# FIDO2AUTH_002.net
KiCad netlist of a schematic drawn in EAGLE
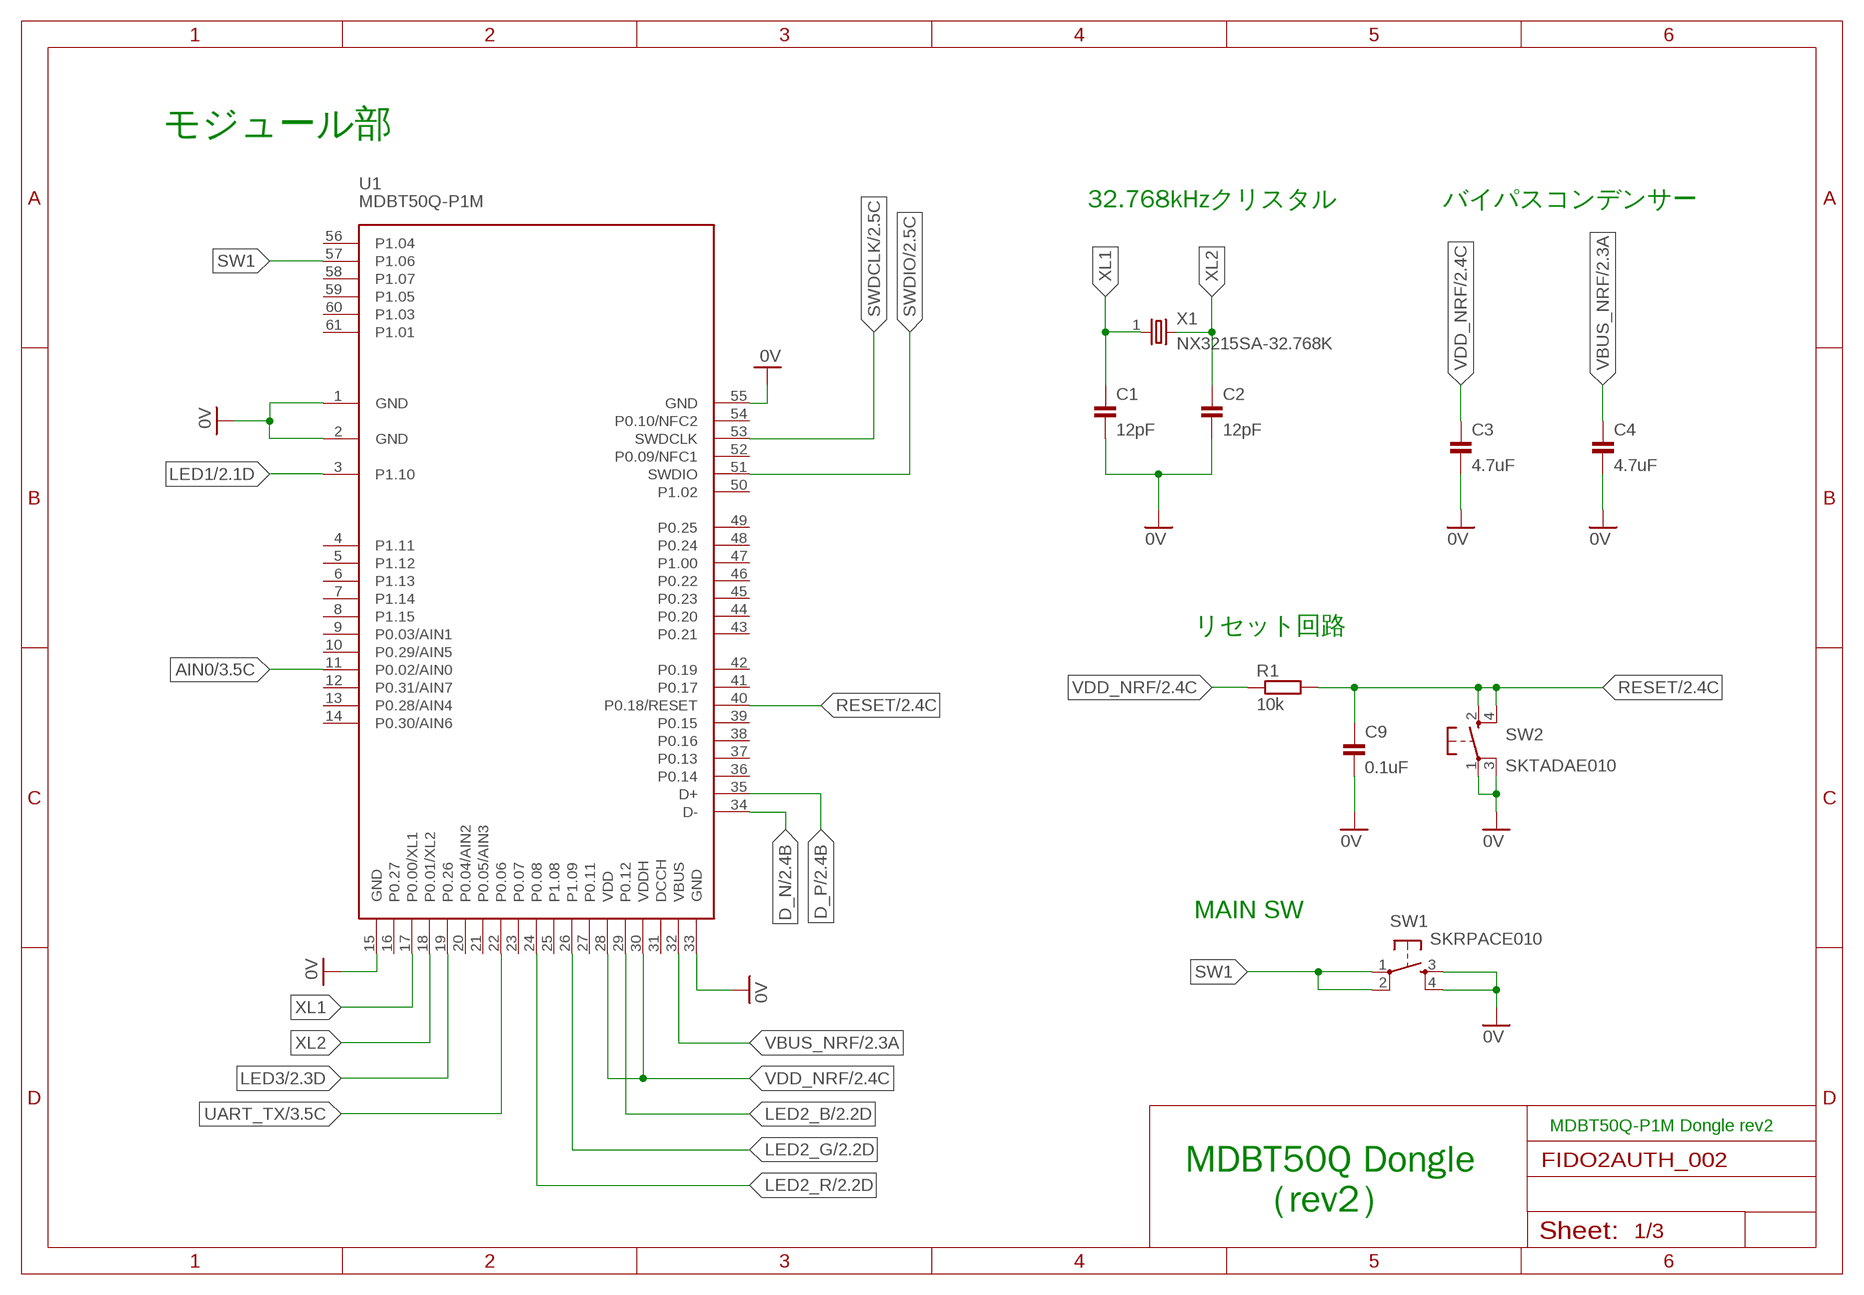
[diagram p0: schematic, sheet 1]
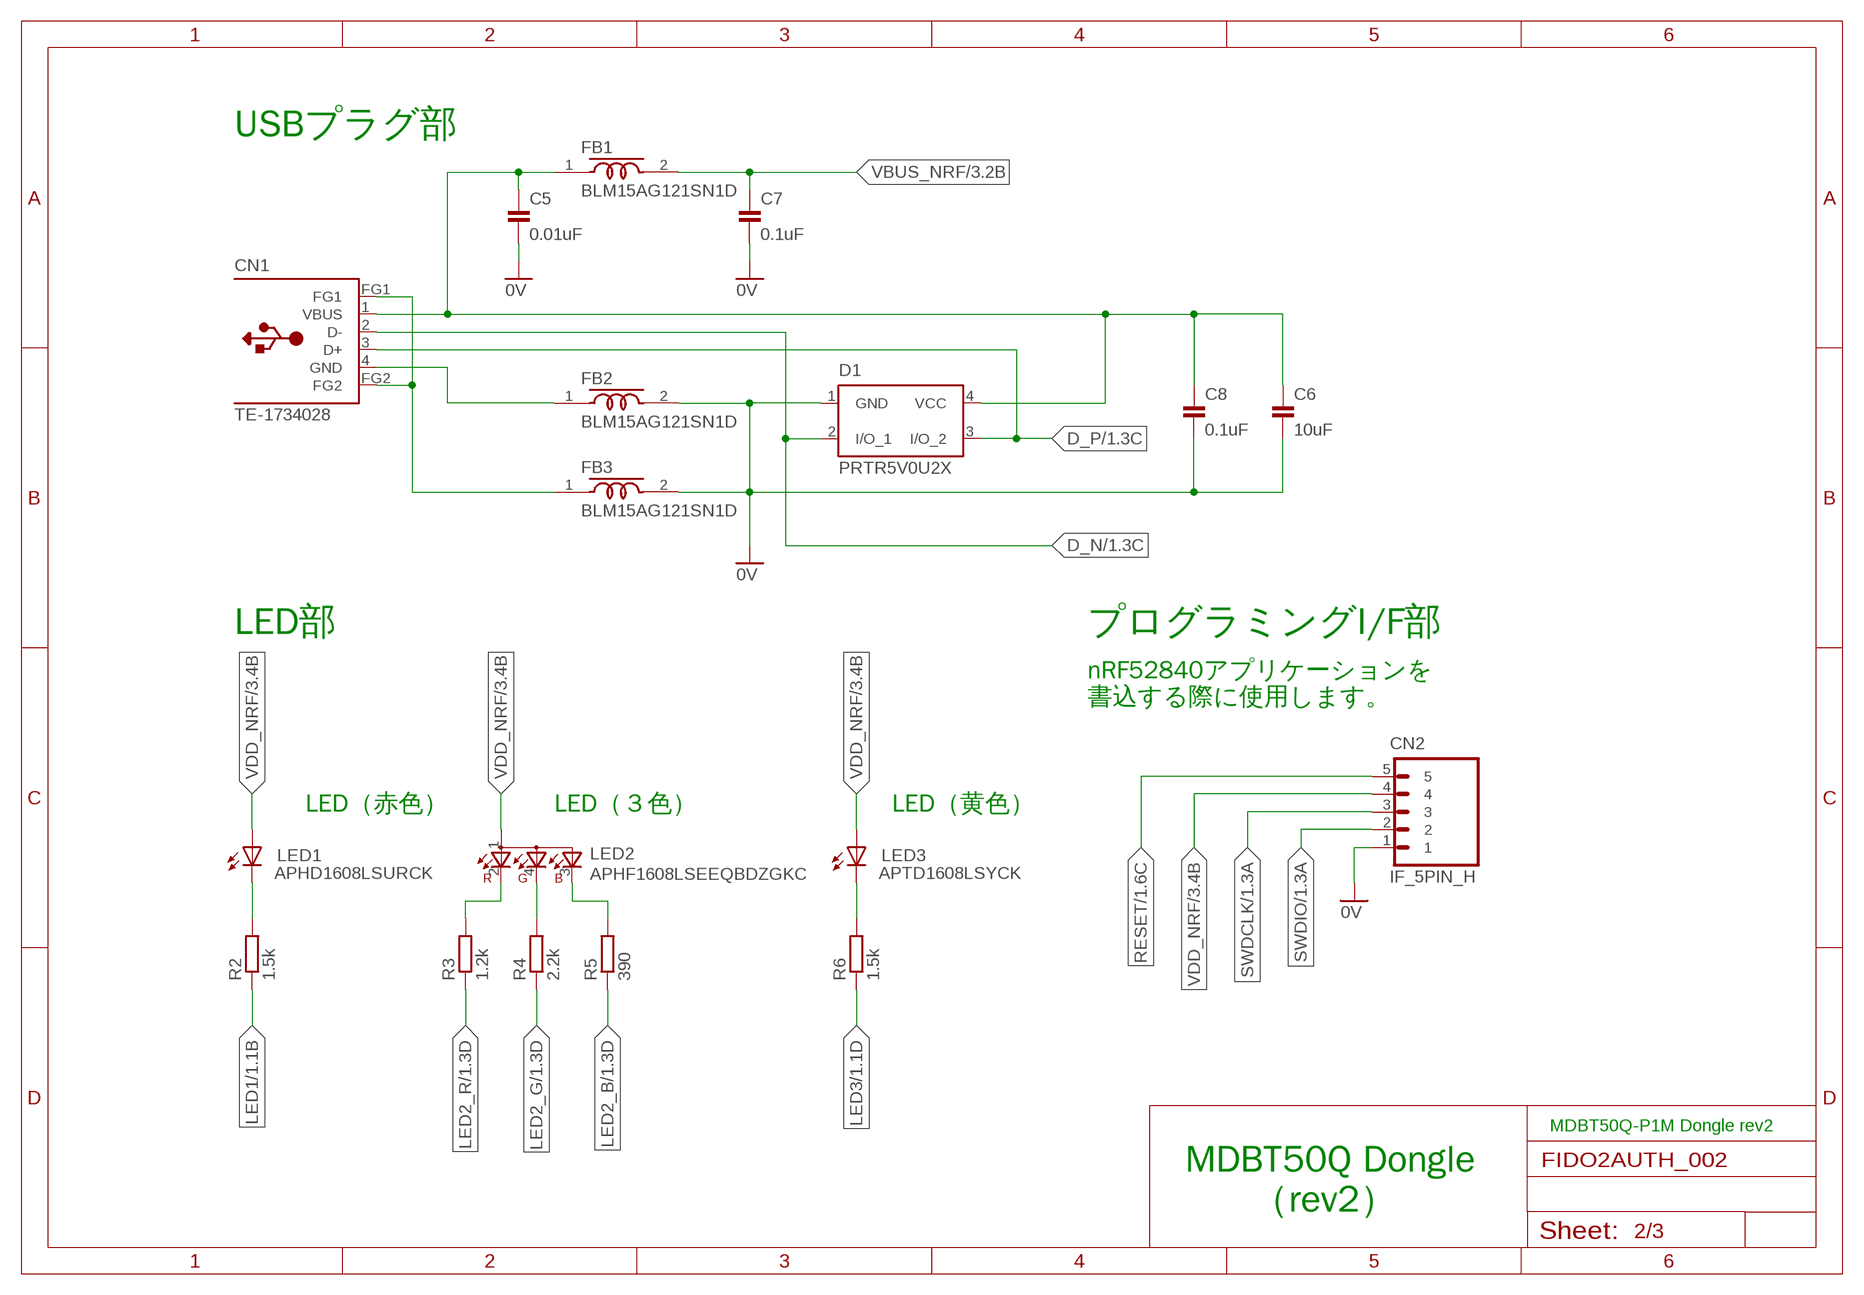
[diagram p1: schematic, sheet 2]
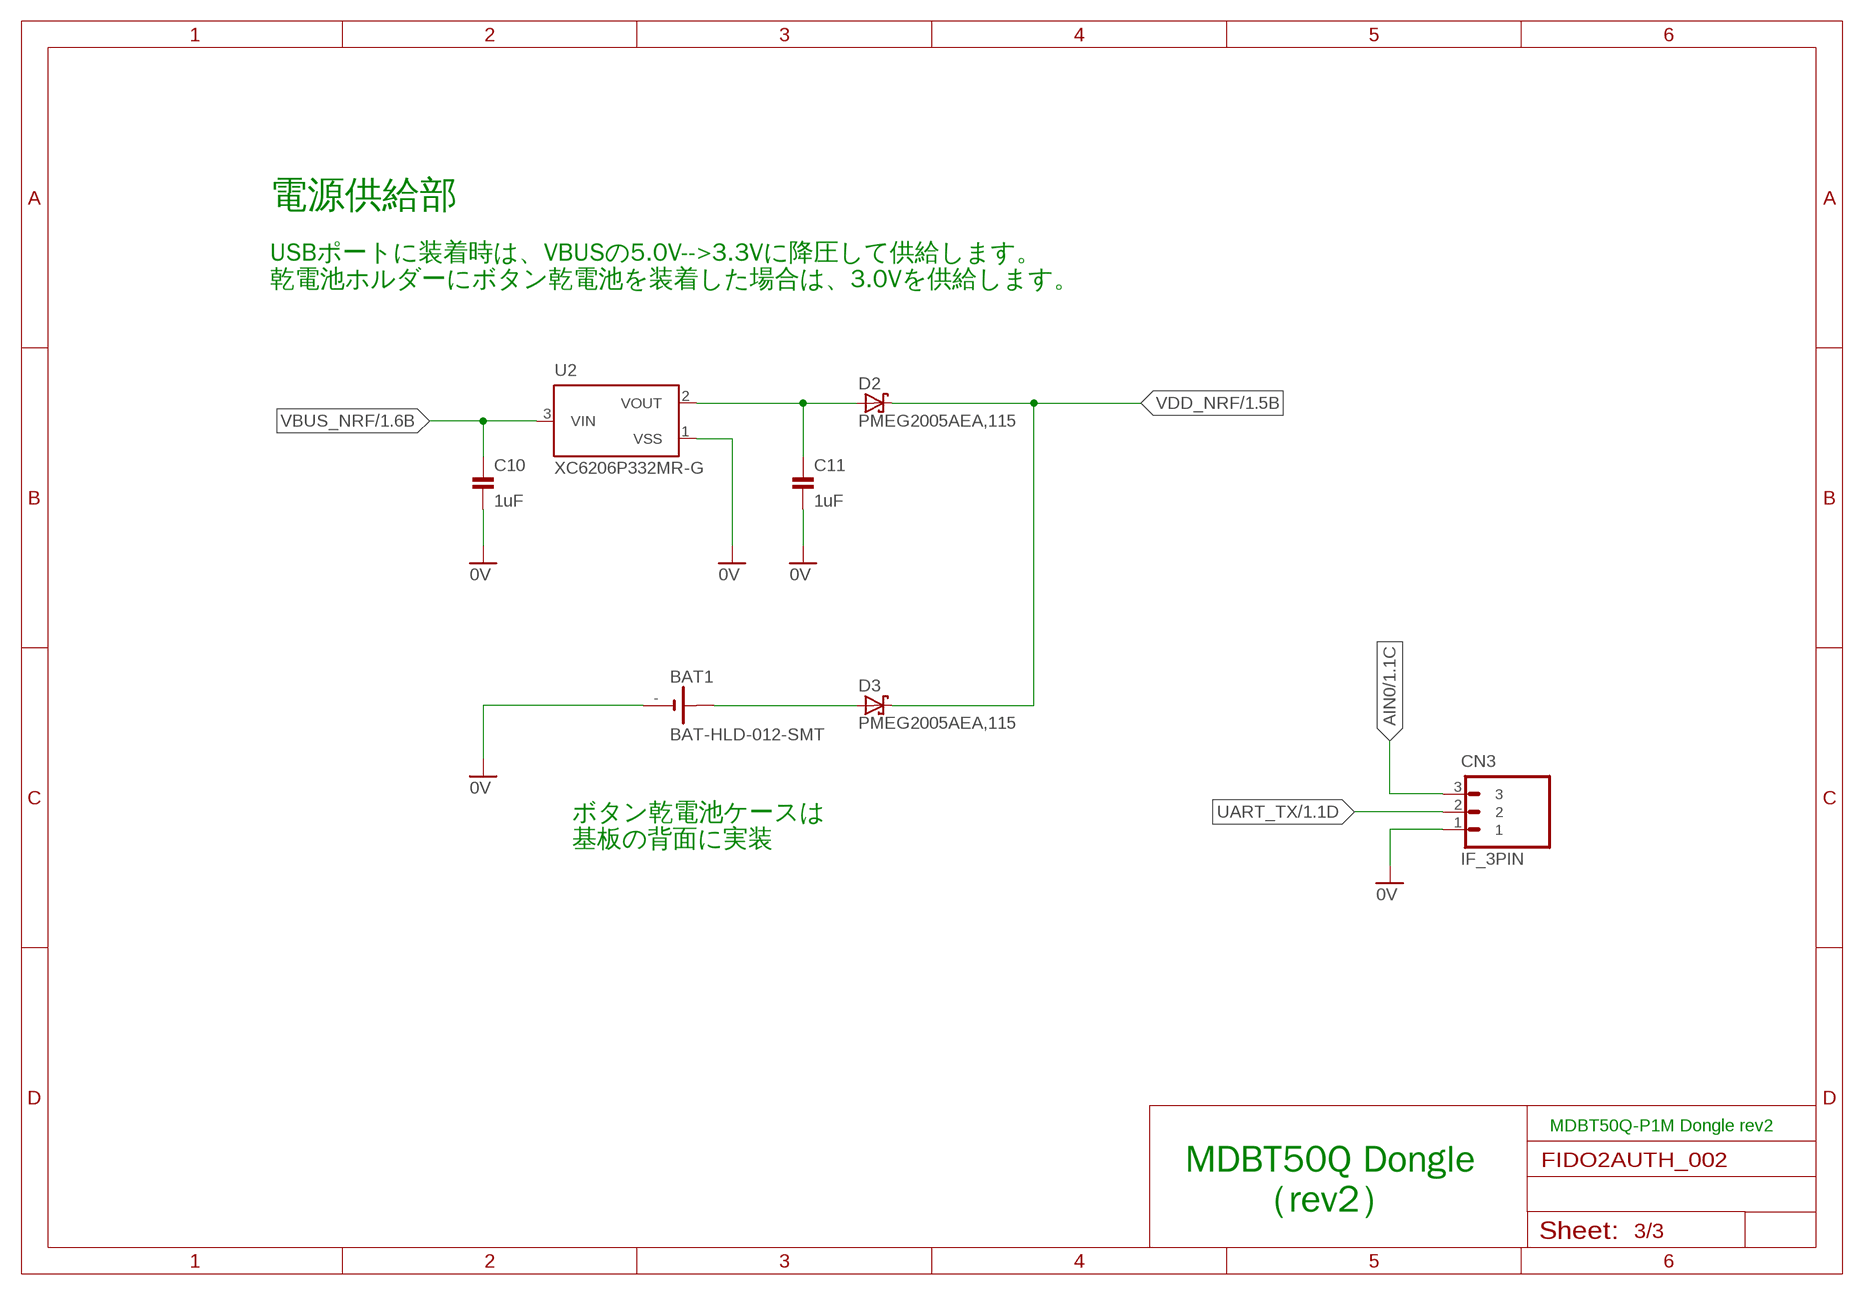
[diagram p2: schematic, sheet 3]

(export (version "E")
  (design (tool "Eeschema 10.0.6"))
  (components
    (comp (ref "BAT1")
      (value "BAT-HLD-012-SMT")
      (footprint "eagle-import:BAT-HLD-012-SMT")
      (libsource (lib "eagle-import") (part "BAT-HLD-012-SMT"))
    )
    (comp (ref "C10")
      (value "1uF")
      (footprint "eagle-import:C0603K")
      (libsource (lib "eagle-import") (part "CAP_0603"))
    )
    (comp (ref "C11")
      (value "1uF")
      (footprint "eagle-import:C0603K")
      (libsource (lib "eagle-import") (part "CAP_0603"))
    )
    (comp (ref "CN3")
      (value "IF_3PIN")
      (footprint "eagle-import:HEADER_3PIN")
      (libsource (lib "eagle-import") (part "IF_3PIN"))
    )
    (comp (ref "D2")
      (value "PMEG2005AEA,115")
      (footprint "eagle-import:SOD323-W")
      (libsource (lib "eagle-import") (part "PMEG2005AEA,115"))
    )
    (comp (ref "D3")
      (value "PMEG2005AEA,115")
      (footprint "eagle-import:SOD323-W")
      (libsource (lib "eagle-import") (part "PMEG2005AEA,115"))
    )
    (comp (ref "U2")
      (value "XC6206P332MR-G")
      (footprint "eagle-import:SOT23")
      (libsource (lib "eagle-import") (part "XC6206P332MR-G"))
    )
    (comp (ref "C5")
      (value "0.01uF")
      (footprint "eagle-import:C0603K")
      (libsource (lib "eagle-import") (part "CAP_0603"))
    )
    (comp (ref "C6")
      (value "10uF")
      (footprint "eagle-import:C0603K")
      (libsource (lib "eagle-import") (part "CAP_0603"))
    )
    (comp (ref "C7")
      (value "0.1uF")
      (footprint "eagle-import:C0603K")
      (libsource (lib "eagle-import") (part "CAP_0603"))
    )
    (comp (ref "C8")
      (value "0.1uF")
      (footprint "eagle-import:C0603K")
      (libsource (lib "eagle-import") (part "CAP_0603"))
    )
    (comp (ref "CN1")
      (value "TE-1734028")
      (footprint "eagle-import:TE-1734028")
      (libsource (lib "eagle-import") (part "TE-1734028"))
    )
    (comp (ref "CN2")
      (value "IF_5PIN_H")
      (footprint "eagle-import:HEADER_5PIN")
      (libsource (lib "eagle-import") (part "IF_5PIN_H"))
    )
    (comp (ref "D1")
      (value "PRTR5V0U2X")
      (footprint "eagle-import:SOT143B")
      (libsource (lib "eagle-import") (part "PRTR5V0U2X"))
    )
    (comp (ref "FB1")
      (value "BLM15AG121SN1D")
      (footprint "eagle-import:C0402K@1")
      (libsource (lib "eagle-import") (part "BLM15AG121SN1D"))
    )
    (comp (ref "FB2")
      (value "BLM15AG121SN1D")
      (footprint "eagle-import:C0402K@1")
      (libsource (lib "eagle-import") (part "BLM15AG121SN1D"))
    )
    (comp (ref "FB3")
      (value "BLM15AG121SN1D")
      (footprint "eagle-import:C0402K@1")
      (libsource (lib "eagle-import") (part "BLM15AG121SN1D"))
    )
    (comp (ref "LED1")
      (value "APHD1608LSURCK")
      (footprint "eagle-import:CHIPLED_0603")
      (libsource (lib "eagle-import") (part "APHD1608LSURCK"))
    )
    (comp (ref "LED2")
      (value "APHF1608LSEEQBDZGKC")
      (footprint "eagle-import:APHF1608LSEEQBDZGKC")
      (libsource (lib "eagle-import") (part "APHF1608LSEEQBDZGKC"))
    )
    (comp (ref "LED3")
      (value "APTD1608LSYCK")
      (footprint "eagle-import:CHIPLED_0603")
      (libsource (lib "eagle-import") (part "APTD1608LSYCK"))
    )
    (comp (ref "R2")
      (value "1.5k")
      (footprint "eagle-import:R0603")
      (libsource (lib "eagle-import") (part "RESISTOR_0603"))
    )
    (comp (ref "R3")
      (value "1.2k")
      (footprint "eagle-import:R0603")
      (libsource (lib "eagle-import") (part "RESISTOR_0603"))
    )
    (comp (ref "R4")
      (value "2.2k")
      (footprint "eagle-import:R0603")
      (libsource (lib "eagle-import") (part "RESISTOR_0603"))
    )
    (comp (ref "R5")
      (value "390")
      (footprint "eagle-import:R0603")
      (libsource (lib "eagle-import") (part "RESISTOR_0603"))
    )
    (comp (ref "R6")
      (value "1.5k")
      (footprint "eagle-import:R0603")
      (libsource (lib "eagle-import") (part "RESISTOR_0603"))
    )
    (comp (ref "C1")
      (value "12pF")
      (footprint "eagle-import:C0603K")
      (libsource (lib "eagle-import") (part "CAP_0603"))
    )
    (comp (ref "C2")
      (value "12pF")
      (footprint "eagle-import:C0603K")
      (libsource (lib "eagle-import") (part "CAP_0603"))
    )
    (comp (ref "C3")
      (value "4.7uF")
      (footprint "eagle-import:C0603K")
      (libsource (lib "eagle-import") (part "CAP_0603"))
    )
    (comp (ref "C4")
      (value "4.7uF")
      (footprint "eagle-import:C0603K")
      (libsource (lib "eagle-import") (part "CAP_0603"))
    )
    (comp (ref "C9")
      (value "0.1uF")
      (footprint "eagle-import:C0603K")
      (libsource (lib "eagle-import") (part "CAP_0603"))
    )
    (comp (ref "R1")
      (value "10k")
      (footprint "eagle-import:R0603")
      (libsource (lib "eagle-import") (part "RESISTOR_0603"))
    )
    (comp (ref "SW1")
      (value "SKRPACE010")
      (footprint "eagle-import:SKRPACE010")
      (libsource (lib "eagle-import") (part "SKRPACE010"))
    )
    (comp (ref "SW2")
      (value "SKTADAE010")
      (footprint "eagle-import:SKTADAE010")
      (libsource (lib "eagle-import") (part "SKTADAE010"))
    )
    (comp (ref "U1")
      (value "MDBT50Q-P1M")
      (footprint "eagle-import:MDBT50Q-P1M")
      (libsource (lib "eagle-import") (part "MDBT50Q-P1M"))
    )
    (comp (ref "X1")
      (value "NX3215SA-32.768K")
      (footprint "eagle-import:NX3215")
      (libsource (lib "eagle-import") (part "NX3215SA-32.768K"))
    )
  )
  (nets
    (net (code "1") (name "0V") (class "Default")
      (node (ref "BAT1") (pin "-") (pinfunction "-_-") (pintype "passive"))
      (node (ref "C1") (pin "2") (pinfunction "2_2") (pintype "passive"))
      (node (ref "C10") (pin "2") (pinfunction "2_2") (pintype "passive"))
      (node (ref "C11") (pin "2") (pinfunction "2_2") (pintype "passive"))
      (node (ref "C2") (pin "2") (pinfunction "2_2") (pintype "passive"))
      (node (ref "C3") (pin "2") (pinfunction "2_2") (pintype "passive"))
      (node (ref "C4") (pin "2") (pinfunction "2_2") (pintype "passive"))
      (node (ref "C5") (pin "2") (pinfunction "2_2") (pintype "passive"))
      (node (ref "C6") (pin "2") (pinfunction "2_2") (pintype "passive"))
      (node (ref "C7") (pin "2") (pinfunction "2_2") (pintype "passive"))
      (node (ref "C8") (pin "2") (pinfunction "2_2") (pintype "passive"))
      (node (ref "C9") (pin "2") (pinfunction "2_2") (pintype "passive"))
      (node (ref "CN2") (pin "1") (pinfunction "1_1") (pintype "passive"))
      (node (ref "CN3") (pin "1") (pinfunction "1_1") (pintype "passive"))
      (node (ref "D1") (pin "1") (pinfunction "GND_1") (pintype "passive"))
      (node (ref "FB2") (pin "2") (pinfunction "2_2") (pintype "passive"))
      (node (ref "FB3") (pin "2") (pinfunction "2_2") (pintype "passive"))
      (node (ref "SW1") (pin "3") (pinfunction "S_3") (pintype "passive"))
      (node (ref "SW1") (pin "4") (pinfunction "S1_4") (pintype "passive"))
      (node (ref "SW2") (pin "1") (pinfunction "P_1") (pintype "passive"))
      (node (ref "SW2") (pin "3") (pinfunction "P1_3") (pintype "passive"))
      (node (ref "U1") (pin "1") (pinfunction "GND_1") (pintype "bidirectional"))
      (node (ref "U1") (pin "15") (pinfunction "GND_15") (pintype "bidirectional"))
      (node (ref "U1") (pin "2") (pinfunction "GND_2") (pintype "bidirectional"))
      (node (ref "U1") (pin "33") (pinfunction "GND_33") (pintype "bidirectional"))
      (node (ref "U1") (pin "55") (pinfunction "GND_55") (pintype "bidirectional"))
      (node (ref "U2") (pin "1") (pinfunction "VSS_1") (pintype "passive"))
    )
    (net (code "2") (name "AIN0") (class "Default")
      (node (ref "CN3") (pin "3") (pinfunction "3_3") (pintype "passive"))
      (node (ref "U1") (pin "11") (pinfunction "P0.02/AIN0_11") (pintype "bidirectional"))
    )
    (net (code "3") (name "D_N") (class "Default")
      (node (ref "CN1") (pin "2") (pinfunction "D-_2") (pintype "bidirectional"))
      (node (ref "D1") (pin "2") (pinfunction "I/O_1_2") (pintype "bidirectional"))
      (node (ref "U1") (pin "34") (pinfunction "D-_34") (pintype "bidirectional"))
    )
    (net (code "4") (name "D_P") (class "Default")
      (node (ref "CN1") (pin "3") (pinfunction "D+_3") (pintype "bidirectional"))
      (node (ref "D1") (pin "3") (pinfunction "I/O_2_3") (pintype "bidirectional"))
      (node (ref "U1") (pin "35") (pinfunction "D+_35") (pintype "bidirectional"))
    )
    (net (code "5") (name "LED1") (class "Default")
      (node (ref "R2") (pin "1") (pinfunction "1_1") (pintype "passive"))
      (node (ref "U1") (pin "3") (pinfunction "P1.10_3") (pintype "bidirectional"))
    )
    (net (code "6") (name "LED2_B") (class "Default")
      (node (ref "R5") (pin "1") (pinfunction "1_1") (pintype "passive"))
      (node (ref "U1") (pin "29") (pinfunction "P0.12_29") (pintype "bidirectional"))
    )
    (net (code "7") (name "LED2_G") (class "Default")
      (node (ref "R4") (pin "1") (pinfunction "1_1") (pintype "passive"))
      (node (ref "U1") (pin "26") (pinfunction "P1.09_26") (pintype "bidirectional"))
    )
    (net (code "8") (name "LED2_R") (class "Default")
      (node (ref "R3") (pin "1") (pinfunction "1_1") (pintype "passive"))
      (node (ref "U1") (pin "24") (pinfunction "P0.08_24") (pintype "bidirectional"))
    )
    (net (code "9") (name "LED3") (class "Default")
      (node (ref "R6") (pin "1") (pinfunction "1_1") (pintype "passive"))
      (node (ref "U1") (pin "19") (pinfunction "P0.26_19") (pintype "bidirectional"))
    )
    (net (code "10") (name "Net-(BAT1-+)") (class "Default")
      (node (ref "BAT1") (pin "+@1") (pinfunction "+_+@1") (pintype "passive"))
      (node (ref "D3") (pin "A") (pinfunction "A_A") (pintype "passive"))
    )
    (net (code "11") (name "Net-(CN1-GND)") (class "Default")
      (node (ref "CN1") (pin "4") (pinfunction "GND_4") (pintype "passive"))
      (node (ref "FB2") (pin "1") (pinfunction "1_1") (pintype "passive"))
    )
    (net (code "12") (name "Net-(CN1-PadFG1)") (class "Default")
      (node (ref "CN1") (pin "FG1") (pinfunction "FG1_FG1") (pintype "passive"))
      (node (ref "CN1") (pin "FG2") (pinfunction "FG2_FG2") (pintype "passive"))
      (node (ref "FB3") (pin "1") (pinfunction "1_1") (pintype "passive"))
    )
    (net (code "13") (name "Net-(CN1-VBUS)") (class "Default")
      (node (ref "C5") (pin "1") (pinfunction "1_1") (pintype "passive"))
      (node (ref "C6") (pin "1") (pinfunction "1_1") (pintype "passive"))
      (node (ref "C8") (pin "1") (pinfunction "1_1") (pintype "passive"))
      (node (ref "CN1") (pin "1") (pinfunction "VBUS_1") (pintype "passive"))
      (node (ref "D1") (pin "4") (pinfunction "VCC_4") (pintype "passive"))
      (node (ref "FB1") (pin "1") (pinfunction "1_1") (pintype "passive"))
    )
    (net (code "14") (name "Net-(LED1-PadC)") (class "Default")
      (node (ref "LED1") (pin "C") (pinfunction "C_C") (pintype "passive"))
      (node (ref "R2") (pin "2") (pinfunction "2_2") (pintype "passive"))
    )
    (net (code "15") (name "Net-(LED2-CBLUE)") (class "Default")
      (node (ref "LED2") (pin "3") (pinfunction "CBLUE_3") (pintype "passive"))
      (node (ref "R5") (pin "2") (pinfunction "2_2") (pintype "passive"))
    )
    (net (code "16") (name "Net-(LED2-CGREEN)") (class "Default")
      (node (ref "LED2") (pin "4") (pinfunction "CGREEN_4") (pintype "passive"))
      (node (ref "R4") (pin "2") (pinfunction "2_2") (pintype "passive"))
    )
    (net (code "17") (name "Net-(LED2-CRED)") (class "Default")
      (node (ref "LED2") (pin "2") (pinfunction "CRED_2") (pintype "passive"))
      (node (ref "R3") (pin "2") (pinfunction "2_2") (pintype "passive"))
    )
    (net (code "18") (name "Net-(LED3-PadC)") (class "Default")
      (node (ref "LED3") (pin "C") (pinfunction "C_C") (pintype "passive"))
      (node (ref "R6") (pin "2") (pinfunction "2_2") (pintype "passive"))
    )
    (net (code "19") (name "Net-(U2-VOUT)") (class "Default")
      (node (ref "C11") (pin "1") (pinfunction "1_1") (pintype "passive"))
      (node (ref "D2") (pin "A") (pinfunction "A_A") (pintype "passive"))
      (node (ref "U2") (pin "2") (pinfunction "VOUT_2") (pintype "passive"))
    )
    (net (code "20") (name "RESET") (class "Default")
      (node (ref "C9") (pin "1") (pinfunction "1_1") (pintype "passive"))
      (node (ref "CN2") (pin "5") (pinfunction "5_5") (pintype "passive"))
      (node (ref "R1") (pin "2") (pinfunction "2_2") (pintype "passive"))
      (node (ref "SW2") (pin "2") (pinfunction "S_2") (pintype "passive"))
      (node (ref "SW2") (pin "4") (pinfunction "S1_4") (pintype "passive"))
      (node (ref "U1") (pin "40") (pinfunction "P0.18/RESET_40") (pintype "bidirectional"))
    )
    (net (code "21") (name "SW1") (class "Default")
      (node (ref "SW1") (pin "1") (pinfunction "P_1") (pintype "passive"))
      (node (ref "SW1") (pin "2") (pinfunction "P1_2") (pintype "passive"))
      (node (ref "U1") (pin "57") (pinfunction "P1.06_57") (pintype "bidirectional"))
    )
    (net (code "22") (name "SWDCLK") (class "Default")
      (node (ref "CN2") (pin "3") (pinfunction "3_3") (pintype "passive"))
      (node (ref "U1") (pin "53") (pinfunction "SWDCLK_53") (pintype "bidirectional"))
    )
    (net (code "23") (name "SWDIO") (class "Default")
      (node (ref "CN2") (pin "2") (pinfunction "2_2") (pintype "passive"))
      (node (ref "U1") (pin "51") (pinfunction "SWDIO_51") (pintype "bidirectional"))
    )
    (net (code "24") (name "UART_TX") (class "Default")
      (node (ref "CN3") (pin "2") (pinfunction "2_2") (pintype "passive"))
      (node (ref "U1") (pin "22") (pinfunction "P0.06_22") (pintype "bidirectional"))
    )
    (net (code "25") (name "VBUS_NRF") (class "Default")
      (node (ref "C10") (pin "1") (pinfunction "1_1") (pintype "passive"))
      (node (ref "C4") (pin "1") (pinfunction "1_1") (pintype "passive"))
      (node (ref "C7") (pin "1") (pinfunction "1_1") (pintype "passive"))
      (node (ref "FB1") (pin "2") (pinfunction "2_2") (pintype "passive"))
      (node (ref "U1") (pin "32") (pinfunction "VBUS_32") (pintype "bidirectional"))
      (node (ref "U2") (pin "3") (pinfunction "VIN_3") (pintype "passive"))
    )
    (net (code "26") (name "VDD_NRF") (class "Default")
      (node (ref "C3") (pin "1") (pinfunction "1_1") (pintype "passive"))
      (node (ref "CN2") (pin "4") (pinfunction "4_4") (pintype "passive"))
      (node (ref "D2") (pin "C") (pinfunction "C_C") (pintype "passive"))
      (node (ref "D3") (pin "C") (pinfunction "C_C") (pintype "passive"))
      (node (ref "LED1") (pin "A") (pinfunction "A_A") (pintype "passive"))
      (node (ref "LED2") (pin "1") (pinfunction "A_1") (pintype "passive"))
      (node (ref "LED3") (pin "A") (pinfunction "A_A") (pintype "passive"))
      (node (ref "R1") (pin "1") (pinfunction "1_1") (pintype "passive"))
      (node (ref "U1") (pin "28") (pinfunction "VDD_28") (pintype "bidirectional"))
      (node (ref "U1") (pin "30") (pinfunction "VDDH_30") (pintype "bidirectional"))
    )
    (net (code "27") (name "XL1") (class "Default")
      (node (ref "C1") (pin "1") (pinfunction "1_1") (pintype "passive"))
      (node (ref "U1") (pin "17") (pinfunction "P0.00/XL1_17") (pintype "bidirectional"))
      (node (ref "X1") (pin "1") (pinfunction "1_1") (pintype "passive"))
    )
    (net (code "28") (name "XL2") (class "Default")
      (node (ref "C2") (pin "1") (pinfunction "1_1") (pintype "passive"))
      (node (ref "U1") (pin "18") (pinfunction "P0.01/XL2_18") (pintype "bidirectional"))
      (node (ref "X1") (pin "2") (pinfunction "2_2") (pintype "passive"))
    )
    (net (code "29") (name "unconnected-(U1-DCCH-Pad31)") (class "Default")
      (node (ref "U1") (pin "31") (pinfunction "DCCH_31") (pintype "bidirectional"))
    )
    (net (code "30") (name "unconnected-(U1-P0.03{slash}AIN1-Pad9)") (class "Default")
      (node (ref "U1") (pin "9") (pinfunction "P0.03/AIN1_9") (pintype "bidirectional"))
    )
    (net (code "31") (name "unconnected-(U1-P0.04{slash}AIN2-Pad20)") (class "Default")
      (node (ref "U1") (pin "20") (pinfunction "P0.04/AIN2_20") (pintype "bidirectional"))
    )
    (net (code "32") (name "unconnected-(U1-P0.05{slash}AIN3-Pad21)") (class "Default")
      (node (ref "U1") (pin "21") (pinfunction "P0.05/AIN3_21") (pintype "bidirectional"))
    )
    (net (code "33") (name "unconnected-(U1-P0.07-Pad23)") (class "Default")
      (node (ref "U1") (pin "23") (pinfunction "P0.07_23") (pintype "bidirectional"))
    )
    (net (code "34") (name "unconnected-(U1-P0.09{slash}NFC1-Pad52)") (class "Default")
      (node (ref "U1") (pin "52") (pinfunction "P0.09/NFC1_52") (pintype "bidirectional"))
    )
    (net (code "35") (name "unconnected-(U1-P0.10{slash}NFC2-Pad54)") (class "Default")
      (node (ref "U1") (pin "54") (pinfunction "P0.10/NFC2_54") (pintype "bidirectional"))
    )
    (net (code "36") (name "unconnected-(U1-P0.11-Pad27)") (class "Default")
      (node (ref "U1") (pin "27") (pinfunction "P0.11_27") (pintype "bidirectional"))
    )
    (net (code "37") (name "unconnected-(U1-P0.13-Pad37)") (class "Default")
      (node (ref "U1") (pin "37") (pinfunction "P0.13_37") (pintype "bidirectional"))
    )
    (net (code "38") (name "unconnected-(U1-P0.14-Pad36)") (class "Default")
      (node (ref "U1") (pin "36") (pinfunction "P0.14_36") (pintype "bidirectional"))
    )
    (net (code "39") (name "unconnected-(U1-P0.15-Pad39)") (class "Default")
      (node (ref "U1") (pin "39") (pinfunction "P0.15_39") (pintype "bidirectional"))
    )
    (net (code "40") (name "unconnected-(U1-P0.16-Pad38)") (class "Default")
      (node (ref "U1") (pin "38") (pinfunction "P0.16_38") (pintype "bidirectional"))
    )
    (net (code "41") (name "unconnected-(U1-P0.17-Pad41)") (class "Default")
      (node (ref "U1") (pin "41") (pinfunction "P0.17_41") (pintype "bidirectional"))
    )
    (net (code "42") (name "unconnected-(U1-P0.19-Pad42)") (class "Default")
      (node (ref "U1") (pin "42") (pinfunction "P0.19_42") (pintype "bidirectional"))
    )
    (net (code "43") (name "unconnected-(U1-P0.20-Pad44)") (class "Default")
      (node (ref "U1") (pin "44") (pinfunction "P0.20_44") (pintype "bidirectional"))
    )
    (net (code "44") (name "unconnected-(U1-P0.21-Pad43)") (class "Default")
      (node (ref "U1") (pin "43") (pinfunction "P0.21_43") (pintype "bidirectional"))
    )
    (net (code "45") (name "unconnected-(U1-P0.22-Pad46)") (class "Default")
      (node (ref "U1") (pin "46") (pinfunction "P0.22_46") (pintype "bidirectional"))
    )
    (net (code "46") (name "unconnected-(U1-P0.23-Pad45)") (class "Default")
      (node (ref "U1") (pin "45") (pinfunction "P0.23_45") (pintype "bidirectional"))
    )
    (net (code "47") (name "unconnected-(U1-P0.24-Pad48)") (class "Default")
      (node (ref "U1") (pin "48") (pinfunction "P0.24_48") (pintype "bidirectional"))
    )
    (net (code "48") (name "unconnected-(U1-P0.25-Pad49)") (class "Default")
      (node (ref "U1") (pin "49") (pinfunction "P0.25_49") (pintype "bidirectional"))
    )
    (net (code "49") (name "unconnected-(U1-P0.27-Pad16)") (class "Default")
      (node (ref "U1") (pin "16") (pinfunction "P0.27_16") (pintype "bidirectional"))
    )
    (net (code "50") (name "unconnected-(U1-P0.28{slash}AIN4-Pad13)") (class "Default")
      (node (ref "U1") (pin "13") (pinfunction "P0.28/AIN4_13") (pintype "bidirectional"))
    )
    (net (code "51") (name "unconnected-(U1-P0.29{slash}AIN5-Pad10)") (class "Default")
      (node (ref "U1") (pin "10") (pinfunction "P0.29/AIN5_10") (pintype "bidirectional"))
    )
    (net (code "52") (name "unconnected-(U1-P0.30{slash}AIN6-Pad14)") (class "Default")
      (node (ref "U1") (pin "14") (pinfunction "P0.30/AIN6_14") (pintype "bidirectional"))
    )
    (net (code "53") (name "unconnected-(U1-P0.31{slash}AIN7-Pad12)") (class "Default")
      (node (ref "U1") (pin "12") (pinfunction "P0.31/AIN7_12") (pintype "bidirectional"))
    )
    (net (code "54") (name "unconnected-(U1-P1.00-Pad47)") (class "Default")
      (node (ref "U1") (pin "47") (pinfunction "P1.00_47") (pintype "bidirectional"))
    )
    (net (code "55") (name "unconnected-(U1-P1.01-Pad61)") (class "Default")
      (node (ref "U1") (pin "61") (pinfunction "P1.01_61") (pintype "bidirectional"))
    )
    (net (code "56") (name "unconnected-(U1-P1.02-Pad50)") (class "Default")
      (node (ref "U1") (pin "50") (pinfunction "P1.02_50") (pintype "bidirectional"))
    )
    (net (code "57") (name "unconnected-(U1-P1.03-Pad60)") (class "Default")
      (node (ref "U1") (pin "60") (pinfunction "P1.03_60") (pintype "bidirectional"))
    )
    (net (code "58") (name "unconnected-(U1-P1.04-Pad56)") (class "Default")
      (node (ref "U1") (pin "56") (pinfunction "P1.04_56") (pintype "bidirectional"))
    )
    (net (code "59") (name "unconnected-(U1-P1.05-Pad59)") (class "Default")
      (node (ref "U1") (pin "59") (pinfunction "P1.05_59") (pintype "bidirectional"))
    )
    (net (code "60") (name "unconnected-(U1-P1.07-Pad58)") (class "Default")
      (node (ref "U1") (pin "58") (pinfunction "P1.07_58") (pintype "bidirectional"))
    )
    (net (code "61") (name "unconnected-(U1-P1.08-Pad25)") (class "Default")
      (node (ref "U1") (pin "25") (pinfunction "P1.08_25") (pintype "bidirectional"))
    )
    (net (code "62") (name "unconnected-(U1-P1.11-Pad4)") (class "Default")
      (node (ref "U1") (pin "4") (pinfunction "P1.11_4") (pintype "bidirectional"))
    )
    (net (code "63") (name "unconnected-(U1-P1.12-Pad5)") (class "Default")
      (node (ref "U1") (pin "5") (pinfunction "P1.12_5") (pintype "bidirectional"))
    )
    (net (code "64") (name "unconnected-(U1-P1.13-Pad6)") (class "Default")
      (node (ref "U1") (pin "6") (pinfunction "P1.13_6") (pintype "bidirectional"))
    )
    (net (code "65") (name "unconnected-(U1-P1.14-Pad7)") (class "Default")
      (node (ref "U1") (pin "7") (pinfunction "P1.14_7") (pintype "bidirectional"))
    )
    (net (code "66") (name "unconnected-(U1-P1.15-Pad8)") (class "Default")
      (node (ref "U1") (pin "8") (pinfunction "P1.15_8") (pintype "bidirectional"))
    )
  )
)
